# Sheet3.net
KiCad netlist of a schematic drawn in Altium Designer
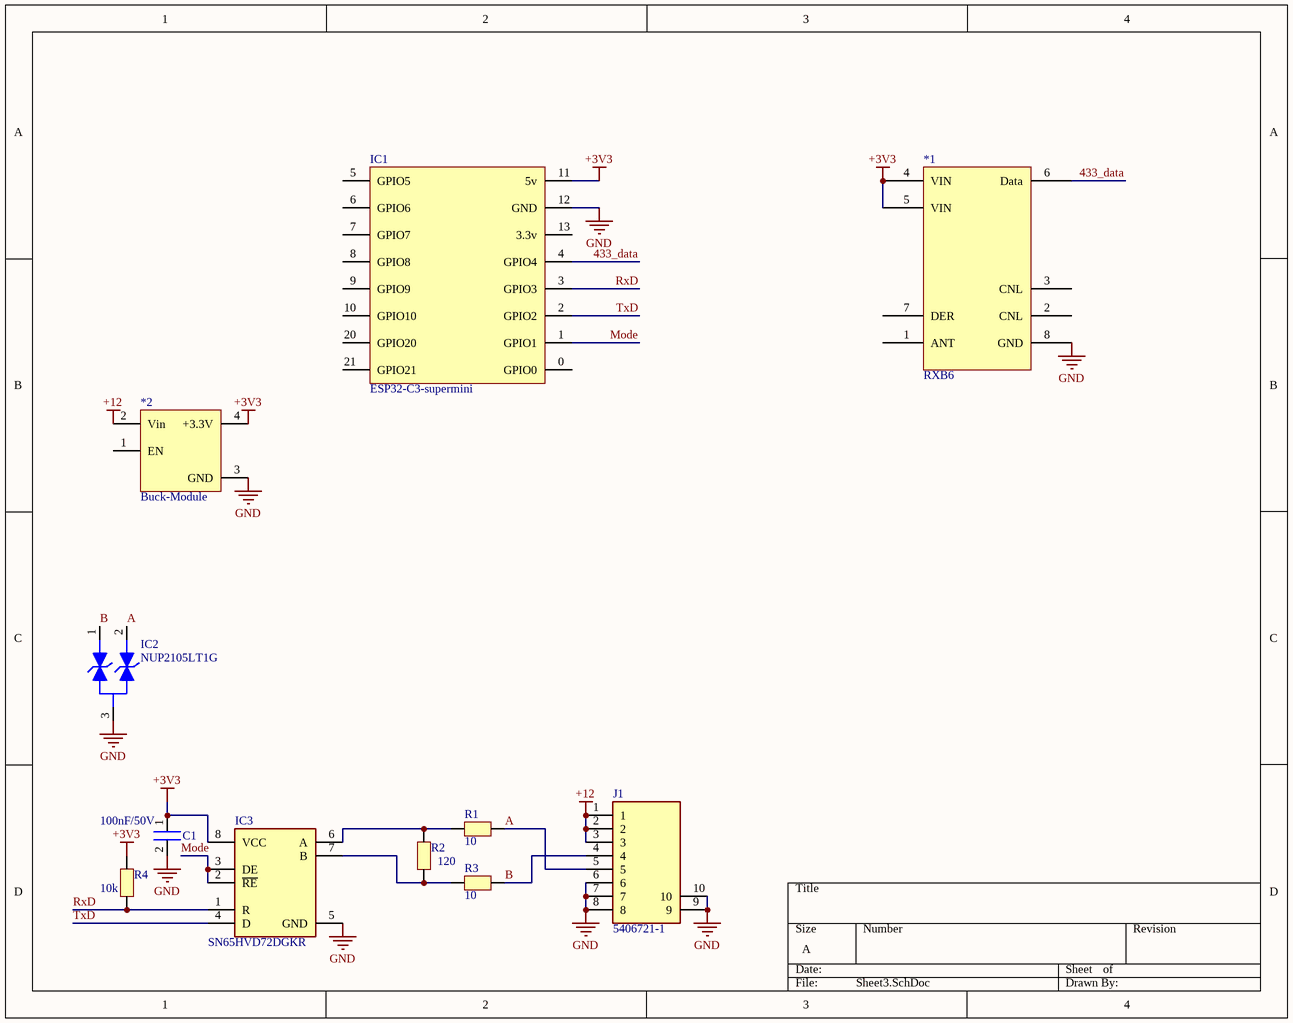
[diagram p0: Sheet3.SchDoc]

(export (version "E")
  (design (tool "Eeschema 10.0.6"))
  (components
    (comp (ref "*1") (value "RXB6") (footprint "RXB6") (libsource (lib "Schlib1") (part "RXB6")))
    (comp (ref "*2")
      (value "Buck-Module")
      (footprint "Buck-Module")
      (libsource (lib "Schlib1") (part "Buck-Module"))
    )
    (comp (ref "C1") (value "100nF/50V") (footprint "Resistor") (libsource (lib "Schlib1") (part "0603 cap")))
    (comp (ref "IC1")
      (value "ESP32-C3-supermini")
      (footprint "Esp32Module")
      (libsource (lib "Schlib1") (part "ESP32-C3-supermini"))
    )
    (comp (ref "IC2")
      (value "NUP2105LT1G")
      (footprint "SamacSys:SOT96P237X111-3N")
      (description "Integrated Circuit")
      (fields (field (name "MOUSER PART NUMBER") "863-NUP2105LT1G"))
      (libsource (lib "Schlib1") (part "NUP2105LT1G"))
    )
    (comp (ref "IC3")
      (value "SN65HVD72DGKR")
      (footprint "SamacSys:SOP65P490X110-8N")
      (description "Integrated Circuit")
      (fields (field (name "MANUFACTURER_PART_NUMBER") "SN65HVD3085EDGKRG4"))
      (libsource (lib "Schlib1") (part "SN65HVD3085EDGKRG4"))
    )
    (comp (ref "J1")
      (value "5406721-1")
      (footprint "SamacSys:54067211")
      (description "Connector")
      (fields (field (name "MOUSER PART NUMBER") "571-5406721-1"))
      (libsource (lib "Schlib1") (part "5406721-1"))
    )
    (comp (ref "R1") (value "10") (footprint "Resistor") (libsource (lib "") (part "Resistor_1")))
    (comp (ref "R2") (value "120") (footprint "Resistor") (libsource (lib "Schlib1") (part "Resistor")))
    (comp (ref "R3") (value "10") (footprint "Resistor") (libsource (lib "") (part "Resistor_1")))
    (comp (ref "R4") (value "10k") (footprint "Resistor") (libsource (lib "Schlib1") (part "Resistor")))
  )
  (nets
    (net (code "1") (name "+3V3") (class "Default")
      (node (ref "*1") (pin "4") (pinfunction "VIN_4") (pintype "passive"))
      (node (ref "*1") (pin "5") (pinfunction "VIN_5") (pintype "passive"))
      (node (ref "*2") (pin "4") (pinfunction "+3.3V_4") (pintype "passive"))
      (node (ref "C1") (pin "1") (pinfunction "38_1") (pintype "passive"))
      (node (ref "IC1") (pin "11") (pinfunction "5v_11") (pintype "passive"))
      (node (ref "IC3") (pin "8") (pinfunction "VCC_8") (pintype "passive"))
      (node (ref "R4") (pin "2") (pinfunction "2_2") (pintype "passive"))
    )
    (net (code "2") (name "+12") (class "Default")
      (node (ref "*2") (pin "2") (pinfunction "Vin_2") (pintype "passive"))
      (node (ref "J1") (pin "1") (pinfunction "1_1") (pintype "passive"))
      (node (ref "J1") (pin "2") (pinfunction "2_2") (pintype "passive"))
      (node (ref "J1") (pin "3") (pinfunction "3_3") (pintype "passive"))
    )
    (net (code "3") (name "/433_data") (class "Default")
      (node (ref "*1") (pin "6") (pinfunction "Data_6") (pintype "passive"))
      (node (ref "IC1") (pin "4") (pinfunction "GPIO4_4") (pintype "passive"))
    )
    (net (code "4") (name "/A") (class "Default")
      (node (ref "IC2") (pin "2") (pinfunction "2_2") (pintype "passive"))
      (node (ref "J1") (pin "5") (pinfunction "5_5") (pintype "passive"))
      (node (ref "R1") (pin "2") (pinfunction "2_2") (pintype "passive"))
    )
    (net (code "5") (name "/B") (class "Default")
      (node (ref "IC2") (pin "1") (pinfunction "1_1") (pintype "passive"))
      (node (ref "J1") (pin "4") (pinfunction "4_4") (pintype "passive"))
      (node (ref "R3") (pin "2") (pinfunction "2_2") (pintype "passive"))
    )
    (net (code "6") (name "/Mode") (class "Default")
      (node (ref "IC1") (pin "1") (pinfunction "GPIO1_1") (pintype "passive"))
      (node (ref "IC3") (pin "2") (pinfunction "~{RE}_2") (pintype "passive"))
      (node (ref "IC3") (pin "3") (pinfunction "DE_3") (pintype "passive"))
    )
    (net (code "7") (name "/RxD") (class "Default")
      (node (ref "IC1") (pin "3") (pinfunction "GPIO3_3") (pintype "passive"))
      (node (ref "IC3") (pin "1") (pinfunction "R_1") (pintype "passive"))
      (node (ref "R4") (pin "1") (pinfunction "1_1") (pintype "passive"))
    )
    (net (code "8") (name "/TxD") (class "Default")
      (node (ref "IC1") (pin "2") (pinfunction "GPIO2_2") (pintype "passive"))
      (node (ref "IC3") (pin "4") (pinfunction "D_4") (pintype "passive"))
    )
    (net (code "9") (name "GND") (class "Default")
      (node (ref "*1") (pin "8") (pinfunction "GND_8") (pintype "passive"))
      (node (ref "*2") (pin "3") (pinfunction "GND_3") (pintype "passive"))
      (node (ref "C1") (pin "2") (pinfunction "39_2") (pintype "passive"))
      (node (ref "IC1") (pin "12") (pinfunction "GND_12") (pintype "passive"))
      (node (ref "IC2") (pin "3") (pinfunction "3_3") (pintype "passive"))
      (node (ref "IC3") (pin "5") (pinfunction "GND_5") (pintype "passive"))
      (node (ref "J1") (pin "10") (pinfunction "10_10") (pintype "passive"))
      (node (ref "J1") (pin "6") (pinfunction "6_6") (pintype "passive"))
      (node (ref "J1") (pin "7") (pinfunction "7_7") (pintype "passive"))
      (node (ref "J1") (pin "8") (pinfunction "8_8") (pintype "passive"))
      (node (ref "J1") (pin "9") (pinfunction "9_9") (pintype "passive"))
    )
    (net (code "10") (name "Net-(IC3-A)") (class "Default")
      (node (ref "IC3") (pin "6") (pinfunction "A_6") (pintype "passive"))
      (node (ref "R1") (pin "1") (pinfunction "1_1") (pintype "passive"))
      (node (ref "R2") (pin "2") (pinfunction "2_2") (pintype "passive"))
    )
    (net (code "11") (name "Net-(IC3-B)") (class "Default")
      (node (ref "IC3") (pin "7") (pinfunction "B_7") (pintype "passive"))
      (node (ref "R2") (pin "1") (pinfunction "1_1") (pintype "passive"))
      (node (ref "R3") (pin "1") (pinfunction "1_1") (pintype "passive"))
    )
    (net (code "12") (name "unconnected-(*1-ANT-Pad1)") (class "Default")
      (node (ref "*1") (pin "1") (pinfunction "ANT_1") (pintype "passive"))
    )
    (net (code "13") (name "unconnected-(*1-CNL-Pad2)") (class "Default")
      (node (ref "*1") (pin "2") (pinfunction "CNL_2") (pintype "passive"))
    )
    (net (code "14") (name "unconnected-(*1-CNL-Pad3)") (class "Default")
      (node (ref "*1") (pin "3") (pinfunction "CNL_3") (pintype "passive"))
    )
    (net (code "15") (name "unconnected-(*1-DER-Pad7)") (class "Default")
      (node (ref "*1") (pin "7") (pinfunction "DER_7") (pintype "passive"))
    )
    (net (code "16") (name "unconnected-(*2-EN-Pad1)") (class "Default")
      (node (ref "*2") (pin "1") (pinfunction "EN_1") (pintype "passive"))
    )
    (net (code "17") (name "unconnected-(IC1-3.3v-Pad13)") (class "Default")
      (node (ref "IC1") (pin "13") (pinfunction "3.3v_13") (pintype "passive"))
    )
    (net (code "18") (name "unconnected-(IC1-GPIO0-Pad0)") (class "Default")
      (node (ref "IC1") (pin "0") (pinfunction "GPIO0_0") (pintype "passive"))
    )
    (net (code "19") (name "unconnected-(IC1-GPIO5-Pad5)") (class "Default")
      (node (ref "IC1") (pin "5") (pinfunction "GPIO5_5") (pintype "passive"))
    )
    (net (code "20") (name "unconnected-(IC1-GPIO6-Pad6)") (class "Default")
      (node (ref "IC1") (pin "6") (pinfunction "GPIO6_6") (pintype "passive"))
    )
    (net (code "21") (name "unconnected-(IC1-GPIO7-Pad7)") (class "Default")
      (node (ref "IC1") (pin "7") (pinfunction "GPIO7_7") (pintype "passive"))
    )
    (net (code "22") (name "unconnected-(IC1-GPIO8-Pad8)") (class "Default")
      (node (ref "IC1") (pin "8") (pinfunction "GPIO8_8") (pintype "passive"))
    )
    (net (code "23") (name "unconnected-(IC1-GPIO9-Pad9)") (class "Default")
      (node (ref "IC1") (pin "9") (pinfunction "GPIO9_9") (pintype "passive"))
    )
    (net (code "24") (name "unconnected-(IC1-GPIO10-Pad10)") (class "Default")
      (node (ref "IC1") (pin "10") (pinfunction "GPIO10_10") (pintype "passive"))
    )
    (net (code "25") (name "unconnected-(IC1-GPIO20-Pad20)") (class "Default")
      (node (ref "IC1") (pin "20") (pinfunction "GPIO20_20") (pintype "passive"))
    )
    (net (code "26") (name "unconnected-(IC1-GPIO21-Pad21)") (class "Default")
      (node (ref "IC1") (pin "21") (pinfunction "GPIO21_21") (pintype "passive"))
    )
  )
)
